# UniversalPSU_NoJump.net
KiCad netlist of a schematic drawn in EAGLE
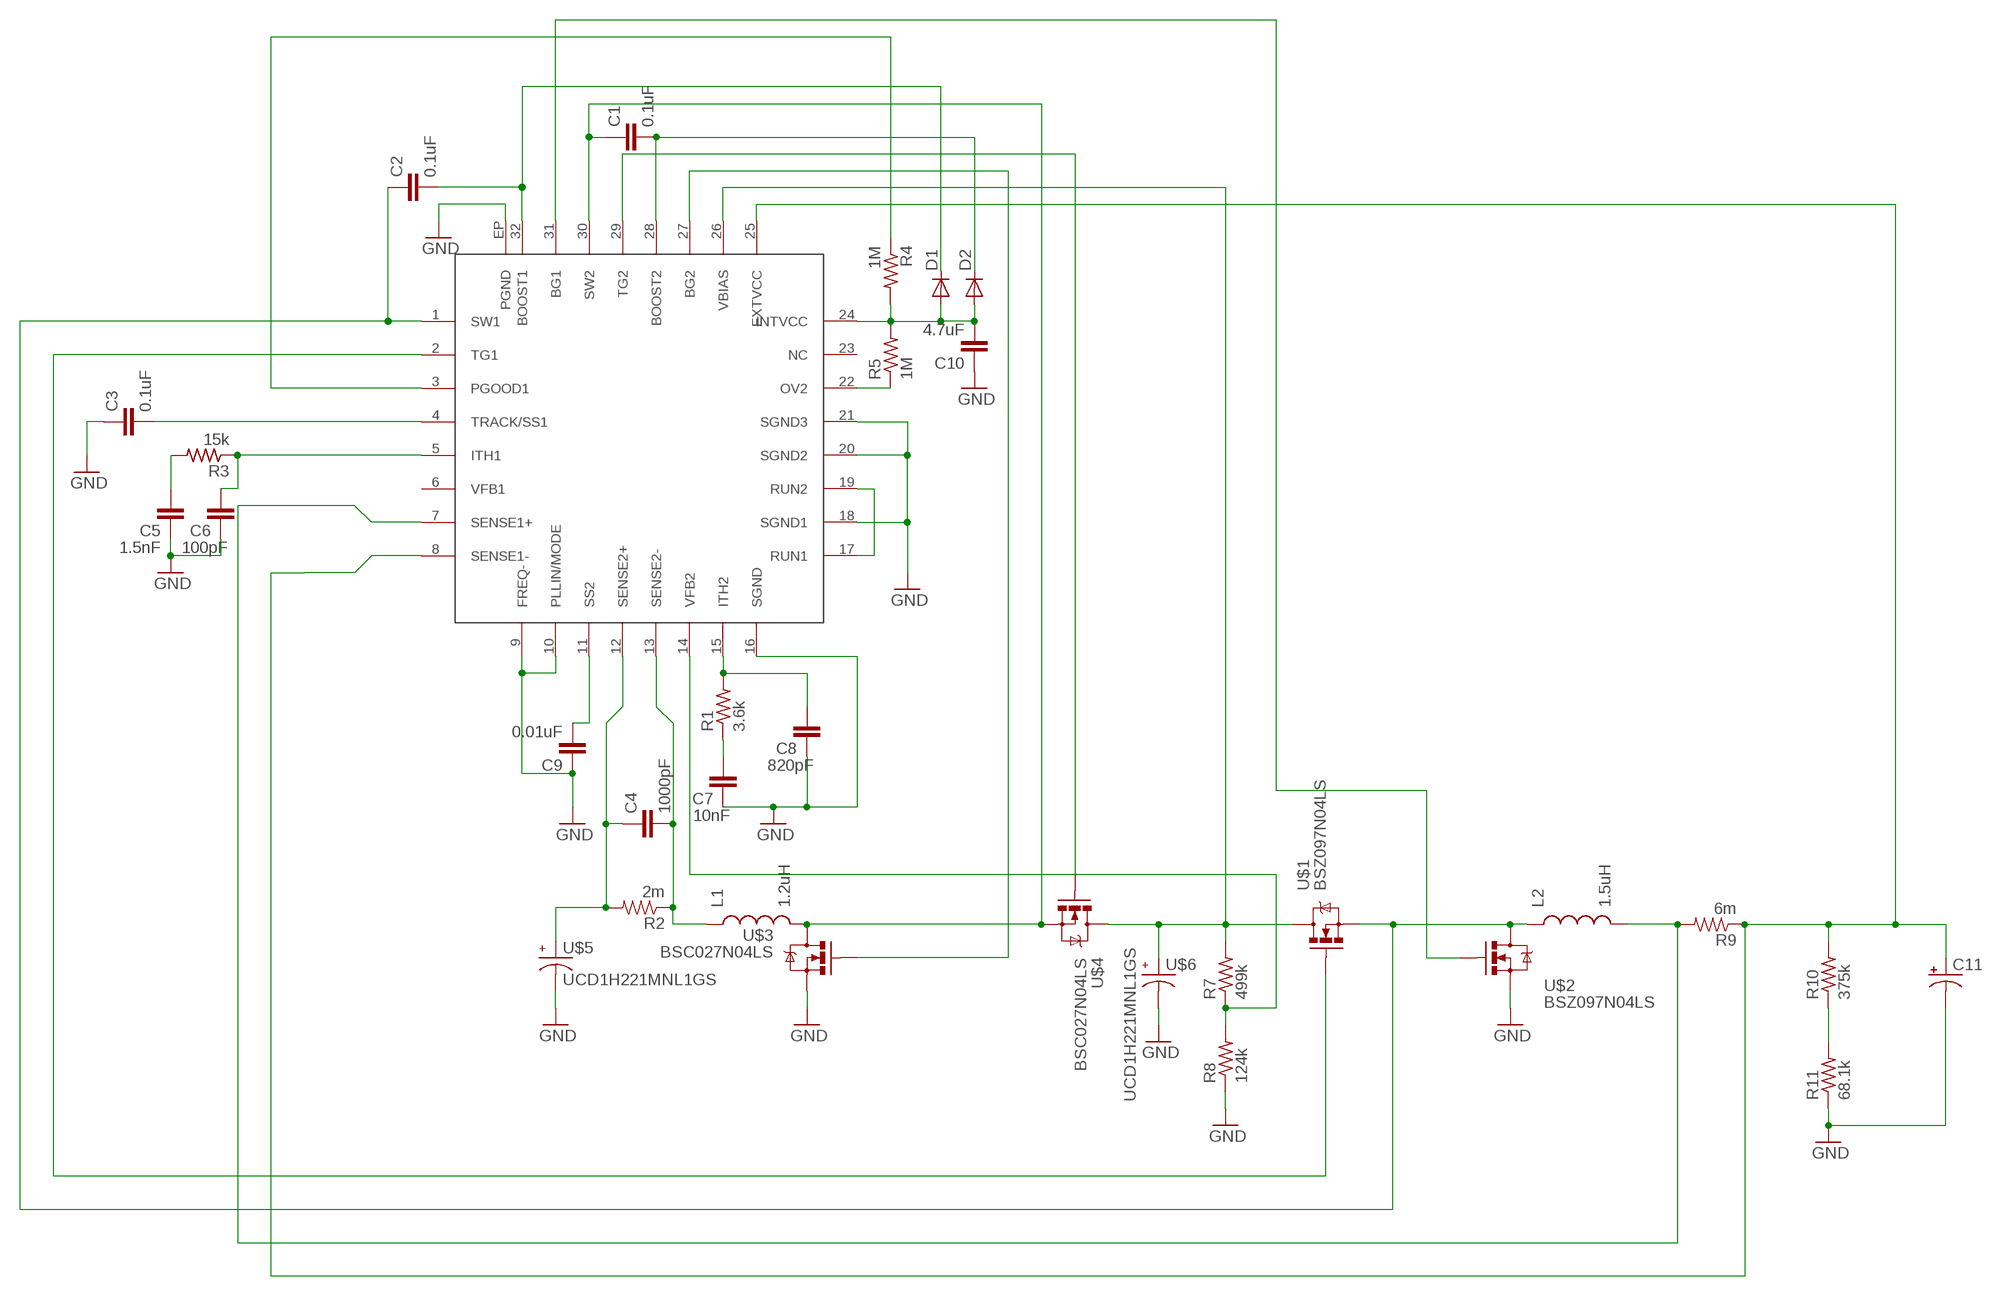
[diagram p0: schematic, sheet 1]

(export (version "E")
  (design (tool "Eeschema 10.0.6"))
  (components
    (comp (ref "C1")
      (value "0.1uF")
      (footprint "eagle-import:C0805")
      (libsource (lib "eagle-import") (part "RF-C0805"))
    )
    (comp (ref "C2")
      (value "0.1uF")
      (footprint "eagle-import:C0805")
      (libsource (lib "eagle-import") (part "RF-C0805"))
    )
    (comp (ref "C3")
      (value "0.1uF")
      (footprint "eagle-import:C0805")
      (libsource (lib "eagle-import") (part "RF-C0805"))
    )
    (comp (ref "C4")
      (value "1000pF")
      (footprint "eagle-import:C0805")
      (libsource (lib "eagle-import") (part "RF-C0805"))
    )
    (comp (ref "C5")
      (value "1.5nF")
      (footprint "eagle-import:C0805")
      (libsource (lib "eagle-import") (part "RF-C0805"))
    )
    (comp (ref "C6")
      (value "100pF")
      (footprint "eagle-import:C0805")
      (libsource (lib "eagle-import") (part "RF-C0805"))
    )
    (comp (ref "C7")
      (value "10nF")
      (footprint "eagle-import:C0805")
      (libsource (lib "eagle-import") (part "RF-C0805"))
    )
    (comp (ref "C8")
      (value "820pF")
      (footprint "eagle-import:C0805")
      (libsource (lib "eagle-import") (part "RF-C0805"))
    )
    (comp (ref "C9")
      (value "0.01uF")
      (footprint "eagle-import:C0805")
      (libsource (lib "eagle-import") (part "RF-C0805"))
    )
    (comp (ref "C10")
      (value "4.7uF")
      (footprint "eagle-import:C0805")
      (libsource (lib "eagle-import") (part "RF-C0805"))
    )
    (comp (ref "C11")
      (value "CAP_POL7343")
      (footprint "eagle-import:EIA7343")
      (libsource (lib "eagle-import") (part "CAP_POL7343"))
    )
    (comp (ref "D1")
      (value "DIODESOD")
      (footprint "eagle-import:SOD-323")
      (libsource (lib "eagle-import") (part "DIODESOD"))
    )
    (comp (ref "D2")
      (value "DIODESOD")
      (footprint "eagle-import:SOD-323")
      (libsource (lib "eagle-import") (part "DIODESOD"))
    )
    (comp (ref "L1")
      (value "1.2uH")
      (footprint "eagle-import:744325120")
      (libsource (lib "eagle-import") (part "INDUCTOR"))
    )
    (comp (ref "L2")
      (value "1.5uH")
      (footprint "eagle-import:744314150")
      (libsource (lib "eagle-import") (part "INDUCTOR-1"))
    )
    (comp (ref "R1")
      (value "3.6k")
      (footprint "eagle-import:RF-C0805")
      (libsource (lib "eagle-import") (part "RF-R0805"))
    )
    (comp (ref "R2")
      (value "2m")
      (footprint "eagle-import:1206")
      (libsource (lib "eagle-import") (part "RESISTOR1206"))
    )
    (comp (ref "R3")
      (value "15k")
      (footprint "eagle-import:RF-C0805")
      (libsource (lib "eagle-import") (part "RF-R0805"))
    )
    (comp (ref "R4")
      (value "1M")
      (footprint "eagle-import:RF-C0805")
      (libsource (lib "eagle-import") (part "RF-R0805"))
    )
    (comp (ref "R5")
      (value "1M")
      (footprint "eagle-import:RF-C0805")
      (libsource (lib "eagle-import") (part "RF-R0805"))
    )
    (comp (ref "R7")
      (value "499k")
      (footprint "eagle-import:RF-C0805")
      (libsource (lib "eagle-import") (part "RF-R0805"))
    )
    (comp (ref "R8")
      (value "124k")
      (footprint "eagle-import:RF-C0805")
      (libsource (lib "eagle-import") (part "RF-R0805"))
    )
    (comp (ref "R9")
      (value "6m")
      (footprint "eagle-import:1206")
      (libsource (lib "eagle-import") (part "RESISTOR1206"))
    )
    (comp (ref "R10")
      (value "375k")
      (footprint "eagle-import:RF-C0805")
      (libsource (lib "eagle-import") (part "RF-R0805"))
    )
    (comp (ref "R11")
      (value "68.1k")
      (footprint "eagle-import:RF-C0805")
      (libsource (lib "eagle-import") (part "RF-R0805"))
    )
    (comp (ref "U$1")
      (value "BSZ097N04LS")
      (footprint "eagle-import:PG-TSDSON-8")
      (libsource (lib "eagle-import") (part "BSZ097N04LS"))
    )
    (comp (ref "U$2")
      (value "BSZ097N04LS")
      (footprint "eagle-import:PG-TSDSON-8")
      (libsource (lib "eagle-import") (part "BSZ097N04LS"))
    )
    (comp (ref "U$3")
      (value "BSC027N04LS")
      (footprint "eagle-import:PG-TSDSON-8")
      (libsource (lib "eagle-import") (part "BSC027N04LS"))
    )
    (comp (ref "U$4")
      (value "BSC027N04LS")
      (footprint "eagle-import:PG-TSDSON-8")
      (libsource (lib "eagle-import") (part "BSC027N04LS"))
    )
    (comp (ref "U$5")
      (value "UCD1H221MNL1GS")
      (footprint "eagle-import:10X10CAP")
      (libsource (lib "eagle-import") (part "UCD1H221MNL1GS"))
    )
    (comp (ref "U$6")
      (value "UCD1H221MNL1GS")
      (footprint "eagle-import:10X10CAP")
      (libsource (lib "eagle-import") (part "UCD1H221MNL1GS"))
    )
    (comp (ref "U1")
      (value "LTC7812")
      (footprint "eagle-import:QFN-32_UH")
      (libsource (lib "eagle-import") (part "LTC7812"))
    )
  )
  (nets
    (net (code "1") (name "GND") (class "Default")
      (node (ref "C10") (pin "1") (pinfunction "1_1") (pintype "passive"))
      (node (ref "C11") (pin "C") (pinfunction "-_C") (pintype "passive"))
      (node (ref "C3") (pin "1") (pinfunction "1_1") (pintype "passive"))
      (node (ref "C5") (pin "1") (pinfunction "1_1") (pintype "passive"))
      (node (ref "C6") (pin "1") (pinfunction "1_1") (pintype "passive"))
      (node (ref "C7") (pin "1") (pinfunction "1_1") (pintype "passive"))
      (node (ref "C8") (pin "1") (pinfunction "1_1") (pintype "passive"))
      (node (ref "C9") (pin "1") (pinfunction "1_1") (pintype "passive"))
      (node (ref "R11") (pin "1") (pinfunction "1_1") (pintype "passive"))
      (node (ref "R8") (pin "1") (pinfunction "1_1") (pintype "passive"))
      (node (ref "U$2") (pin "P$1") (pinfunction "S_P$1") (pintype "passive"))
      (node (ref "U$2") (pin "P$2") (pinfunction "S_P$2") (pintype "passive"))
      (node (ref "U$2") (pin "P$3") (pinfunction "S_P$3") (pintype "passive"))
      (node (ref "U$3") (pin "P$1") (pinfunction "S_P$1") (pintype "passive"))
      (node (ref "U$3") (pin "P$2") (pinfunction "S_P$2") (pintype "passive"))
      (node (ref "U$3") (pin "P$3") (pinfunction "S_P$3") (pintype "passive"))
      (node (ref "U$5") (pin "P$1") (pinfunction "2_P$1") (pintype "passive"))
      (node (ref "U$6") (pin "P$1") (pinfunction "2_P$1") (pintype "passive"))
      (node (ref "U1") (pin "10") (pinfunction "PLLIN/MODE_10") (pintype "bidirectional"))
      (node (ref "U1") (pin "16") (pinfunction "SGND_16") (pintype "bidirectional"))
      (node (ref "U1") (pin "18") (pinfunction "SGND1_18") (pintype "bidirectional"))
      (node (ref "U1") (pin "20") (pinfunction "SGND2_20") (pintype "bidirectional"))
      (node (ref "U1") (pin "21") (pinfunction "SGND3_21") (pintype "bidirectional"))
      (node (ref "U1") (pin "9") (pinfunction "FREQ-_9") (pintype "bidirectional"))
      (node (ref "U1") (pin "EP") (pinfunction "PGND_EP") (pintype "bidirectional"))
    )
    (net (code "2") (name "Net-(C5-Pad2)") (class "Default")
      (node (ref "C5") (pin "2") (pinfunction "2_2") (pintype "passive"))
      (node (ref "R3") (pin "2") (pinfunction "2_2") (pintype "passive"))
    )
    (net (code "3") (name "Net-(C7-Pad2)") (class "Default")
      (node (ref "C7") (pin "2") (pinfunction "2_2") (pintype "passive"))
      (node (ref "R1") (pin "1") (pinfunction "1_1") (pintype "passive"))
    )
    (net (code "4") (name "Net-(C11-+)") (class "Default")
      (node (ref "C11") (pin "A") (pinfunction "+_A") (pintype "passive"))
      (node (ref "R10") (pin "2") (pinfunction "2_2") (pintype "passive"))
      (node (ref "R9") (pin "1") (pinfunction "1_1") (pintype "passive"))
      (node (ref "U1") (pin "25") (pinfunction "EXTVCC_25") (pintype "bidirectional"))
      (node (ref "U1") (pin "8") (pinfunction "SENSE1-_8") (pintype "bidirectional"))
    )
    (net (code "5") (name "Net-(D1-A)") (class "Default")
      (node (ref "C10") (pin "2") (pinfunction "2_2") (pintype "passive"))
      (node (ref "D1") (pin "2") (pinfunction "A_2") (pintype "passive"))
      (node (ref "D2") (pin "2") (pinfunction "A_2") (pintype "passive"))
      (node (ref "R4") (pin "2") (pinfunction "2_2") (pintype "passive"))
      (node (ref "R5") (pin "2") (pinfunction "2_2") (pintype "passive"))
      (node (ref "U1") (pin "24") (pinfunction "INTVCC_24") (pintype "bidirectional"))
    )
    (net (code "6") (name "Net-(D1-C)") (class "Default")
      (node (ref "C2") (pin "2") (pinfunction "2_2") (pintype "passive"))
      (node (ref "D1") (pin "1") (pinfunction "C_1") (pintype "passive"))
      (node (ref "U1") (pin "32") (pinfunction "BOOST1_32") (pintype "bidirectional"))
    )
    (net (code "7") (name "Net-(D2-C)") (class "Default")
      (node (ref "C1") (pin "2") (pinfunction "2_2") (pintype "passive"))
      (node (ref "D2") (pin "1") (pinfunction "C_1") (pintype "passive"))
      (node (ref "U1") (pin "28") (pinfunction "BOOST2_28") (pintype "bidirectional"))
    )
    (net (code "8") (name "Net-(L1-1)") (class "Default")
      (node (ref "C4") (pin "2") (pinfunction "2_2") (pintype "passive"))
      (node (ref "L1") (pin "P$1") (pinfunction "1_P$1") (pintype "passive"))
      (node (ref "R2") (pin "1") (pinfunction "1_1") (pintype "passive"))
      (node (ref "U1") (pin "13") (pinfunction "SENSE2-_13") (pintype "bidirectional"))
    )
    (net (code "9") (name "Net-(L1-2)") (class "Default")
      (node (ref "C1") (pin "1") (pinfunction "1_1") (pintype "passive"))
      (node (ref "L1") (pin "P$2") (pinfunction "2_P$2") (pintype "passive"))
      (node (ref "U$3") (pin "P$5") (pinfunction "D_P$5") (pintype "passive"))
      (node (ref "U$4") (pin "P$1") (pinfunction "S_P$1") (pintype "passive"))
      (node (ref "U$4") (pin "P$2") (pinfunction "S_P$2") (pintype "passive"))
      (node (ref "U$4") (pin "P$3") (pinfunction "S_P$3") (pintype "passive"))
      (node (ref "U1") (pin "30") (pinfunction "SW2_30") (pintype "bidirectional"))
    )
    (net (code "10") (name "Net-(L2-1)") (class "Default")
      (node (ref "C2") (pin "1") (pinfunction "1_1") (pintype "passive"))
      (node (ref "L2") (pin "P$1") (pinfunction "1_P$1") (pintype "passive"))
      (node (ref "U$1") (pin "P$1") (pinfunction "S_P$1") (pintype "passive"))
      (node (ref "U$1") (pin "P$2") (pinfunction "S_P$2") (pintype "passive"))
      (node (ref "U$1") (pin "P$3") (pinfunction "S_P$3") (pintype "passive"))
      (node (ref "U$2") (pin "P$5") (pinfunction "D_P$5") (pintype "passive"))
      (node (ref "U1") (pin "1") (pinfunction "SW1_1") (pintype "bidirectional"))
    )
    (net (code "11") (name "Net-(L2-2)") (class "Default")
      (node (ref "L2") (pin "P$2") (pinfunction "2_P$2") (pintype "passive"))
      (node (ref "R9") (pin "2") (pinfunction "2_2") (pintype "passive"))
      (node (ref "U1") (pin "7") (pinfunction "SENSE1+_7") (pintype "bidirectional"))
    )
    (net (code "12") (name "Net-(R10-Pad1)") (class "Default")
      (node (ref "R10") (pin "1") (pinfunction "1_1") (pintype "passive"))
      (node (ref "R11") (pin "2") (pinfunction "2_2") (pintype "passive"))
    )
    (net (code "13") (name "Net-(U$1-D)") (class "Default")
      (node (ref "R7") (pin "2") (pinfunction "2_2") (pintype "passive"))
      (node (ref "U$1") (pin "P$5") (pinfunction "D_P$5") (pintype "passive"))
      (node (ref "U$4") (pin "P$5") (pinfunction "D_P$5") (pintype "passive"))
      (node (ref "U$6") (pin "P$2") (pinfunction "1_P$2") (pintype "passive"))
      (node (ref "U1") (pin "26") (pinfunction "VBIAS_26") (pintype "bidirectional"))
    )
    (net (code "14") (name "Net-(U$1-G)") (class "Default")
      (node (ref "U$1") (pin "P$4") (pinfunction "G_P$4") (pintype "passive"))
      (node (ref "U1") (pin "2") (pinfunction "TG1_2") (pintype "bidirectional"))
    )
    (net (code "15") (name "Net-(U$2-G)") (class "Default")
      (node (ref "U$2") (pin "P$4") (pinfunction "G_P$4") (pintype "passive"))
      (node (ref "U1") (pin "31") (pinfunction "BG1_31") (pintype "bidirectional"))
    )
    (net (code "16") (name "Net-(U$3-G)") (class "Default")
      (node (ref "U$3") (pin "P$4") (pinfunction "G_P$4") (pintype "passive"))
      (node (ref "U1") (pin "27") (pinfunction "BG2_27") (pintype "bidirectional"))
    )
    (net (code "17") (name "Net-(U$4-G)") (class "Default")
      (node (ref "U$4") (pin "P$4") (pinfunction "G_P$4") (pintype "passive"))
      (node (ref "U1") (pin "29") (pinfunction "TG2_29") (pintype "bidirectional"))
    )
    (net (code "18") (name "Net-(U$5-1)") (class "Default")
      (node (ref "C4") (pin "1") (pinfunction "1_1") (pintype "passive"))
      (node (ref "R2") (pin "2") (pinfunction "2_2") (pintype "passive"))
      (node (ref "U$5") (pin "P$2") (pinfunction "1_P$2") (pintype "passive"))
      (node (ref "U1") (pin "12") (pinfunction "SENSE2+_12") (pintype "bidirectional"))
    )
    (net (code "19") (name "Net-(U1-ITH1)") (class "Default")
      (node (ref "C6") (pin "2") (pinfunction "2_2") (pintype "passive"))
      (node (ref "R3") (pin "1") (pinfunction "1_1") (pintype "passive"))
      (node (ref "U1") (pin "5") (pinfunction "ITH1_5") (pintype "bidirectional"))
    )
    (net (code "20") (name "Net-(U1-ITH2)") (class "Default")
      (node (ref "C8") (pin "2") (pinfunction "2_2") (pintype "passive"))
      (node (ref "R1") (pin "2") (pinfunction "2_2") (pintype "passive"))
      (node (ref "U1") (pin "15") (pinfunction "ITH2_15") (pintype "bidirectional"))
    )
    (net (code "21") (name "Net-(U1-OV2)") (class "Default")
      (node (ref "R5") (pin "1") (pinfunction "1_1") (pintype "passive"))
      (node (ref "U1") (pin "22") (pinfunction "OV2_22") (pintype "bidirectional"))
    )
    (net (code "22") (name "Net-(U1-PGOOD1)") (class "Default")
      (node (ref "R4") (pin "1") (pinfunction "1_1") (pintype "passive"))
      (node (ref "U1") (pin "3") (pinfunction "PGOOD1_3") (pintype "bidirectional"))
    )
    (net (code "23") (name "Net-(U1-RUN1)") (class "Default")
      (node (ref "U1") (pin "17") (pinfunction "RUN1_17") (pintype "bidirectional"))
      (node (ref "U1") (pin "19") (pinfunction "RUN2_19") (pintype "bidirectional"))
    )
    (net (code "24") (name "Net-(U1-SS2)") (class "Default")
      (node (ref "C9") (pin "2") (pinfunction "2_2") (pintype "passive"))
      (node (ref "U1") (pin "11") (pinfunction "SS2_11") (pintype "bidirectional"))
    )
    (net (code "25") (name "Net-(U1-TRACK{slash}SS1)") (class "Default")
      (node (ref "C3") (pin "2") (pinfunction "2_2") (pintype "passive"))
      (node (ref "U1") (pin "4") (pinfunction "TRACK/SS1_4") (pintype "bidirectional"))
    )
    (net (code "26") (name "Net-(U1-VFB2)") (class "Default")
      (node (ref "R7") (pin "1") (pinfunction "1_1") (pintype "passive"))
      (node (ref "R8") (pin "2") (pinfunction "2_2") (pintype "passive"))
      (node (ref "U1") (pin "14") (pinfunction "VFB2_14") (pintype "bidirectional"))
    )
    (net (code "27") (name "unconnected-(U1-NC-Pad23)") (class "Default")
      (node (ref "U1") (pin "23") (pinfunction "NC_23") (pintype "bidirectional"))
    )
    (net (code "28") (name "unconnected-(U1-VFB1-Pad6)") (class "Default")
      (node (ref "U1") (pin "6") (pinfunction "VFB1_6") (pintype "bidirectional"))
    )
  )
)
